# Transceivers.net
KiCad netlist of a schematic drawn in Altium Designer
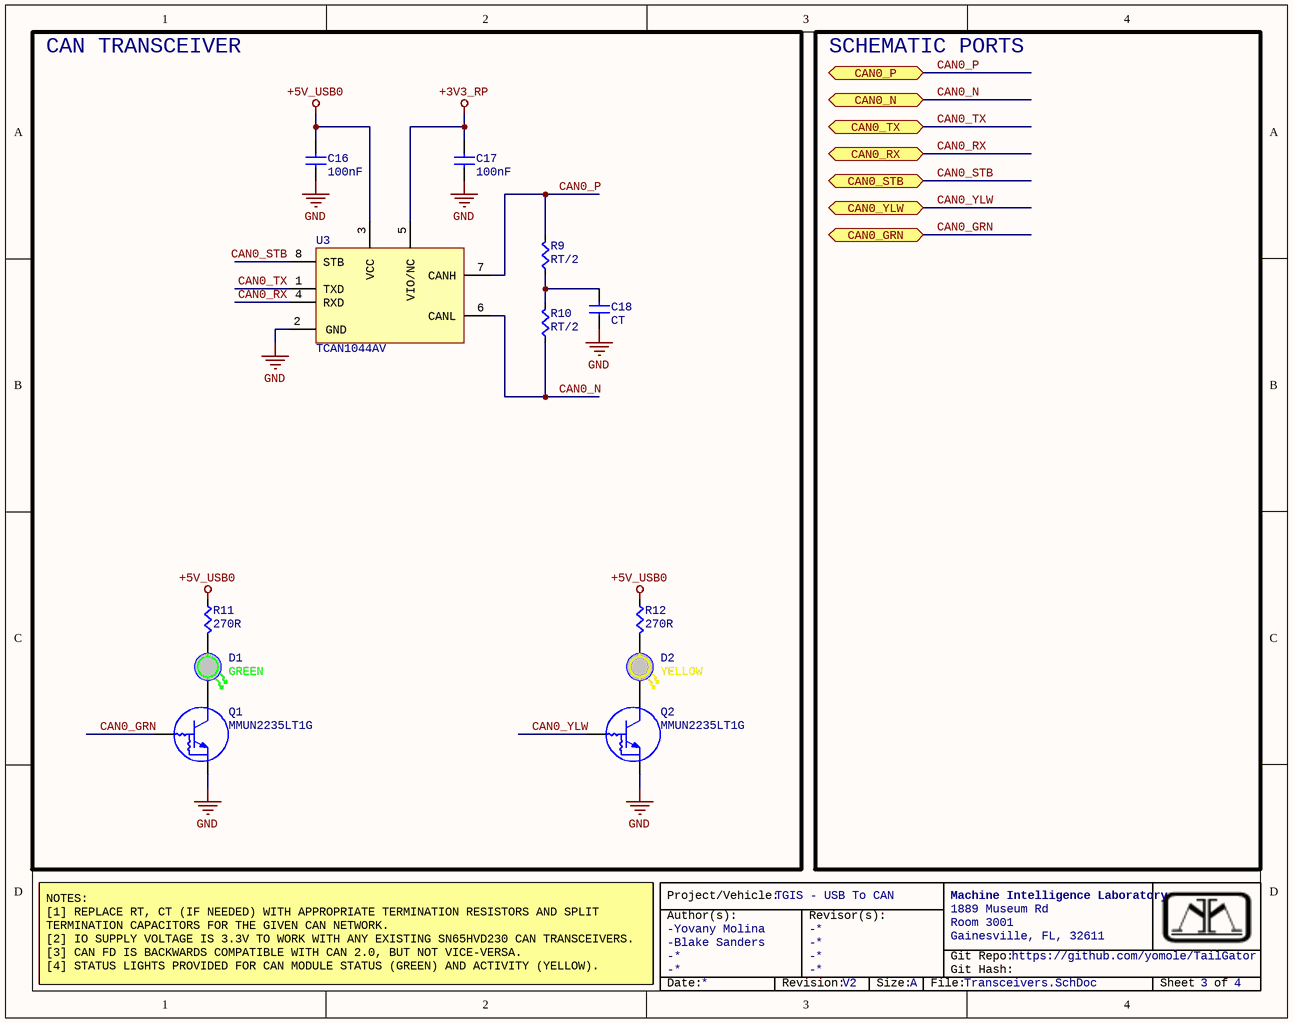
[diagram p0: Transceivers.SchDoc]

(export (version "E")
  (design (tool "Eeschema 10.0.6"))
  (components
    (comp (ref "C16")
      (value "100nF")
      (footprint "CAPC0603")
      (description "Ceramic Capacitor, Multilayer, Cera")
      (fields (field (name "PART NUMBER") "CC0603KRX7R7BB104") (field (name "MANUFACTURER") "Yageo"))
      (libsource (lib "Parts") (part "NP_Capacitor"))
    )
    (comp (ref "C17")
      (value "100nF")
      (footprint "CAPC0603")
      (description "Ceramic Capacitor, Multilayer, Cera")
      (fields (field (name "PART NUMBER") "CC0603KRX7R7BB104") (field (name "MANUFACTURER") "Yageo"))
      (libsource (lib "Parts") (part "NP_Capacitor"))
    )
    (comp (ref "C18")
      (value "CT")
      (footprint "CAPC0603")
      (fields (field (name "Comment") "Cap"))
      (libsource (lib "Passives") (part "Cap"))
    )
    (comp (ref "D1")
      (value "GREEN")
      (footprint "LED0603")
      (description "Single Color LED, Bright Green, Wat")
      (fields (field (name "PART NUMBER") "150060VS75000") (field (name "MANUFACTURER") "Wurth Electronics"))
      (libsource (lib "Parts") (part "LED_Green"))
    )
    (comp (ref "D2")
      (value "YELLOW")
      (footprint "LED0603")
      (description "Single Color LED, Yellow, Water Cle")
      (fields (field (name "PART NUMBER") "150060YS75000") (field (name "MANUFACTURER") "Wurth Electronics"))
      (libsource (lib "Parts") (part "LED_Yellow"))
    )
    (comp (ref "Q1")
      (value "MMUN2235LT1G")
      (footprint "SOT-23-3")
      (description "Small Signal Bipolar Transistor, 0.")
      (fields (field (name "MANUFACTURER") "ON Semiconductor"))
      (libsource (lib "Parts") (part "PB_NPN_Transistor"))
    )
    (comp (ref "Q2")
      (value "MMUN2235LT1G")
      (footprint "SOT-23-3")
      (description "Small Signal Bipolar Transistor, 0.")
      (fields (field (name "MANUFACTURER") "ON Semiconductor"))
      (libsource (lib "Parts") (part "PB_NPN_Transistor"))
    )
    (comp (ref "R9")
      (value "RT/2")
      (footprint "RES0603")
      (fields (field (name "Comment") "Res"))
      (libsource (lib "Passives") (part "Res"))
    )
    (comp (ref "R10")
      (value "RT/2")
      (footprint "RES0603")
      (fields (field (name "Comment") "Res"))
      (libsource (lib "Passives") (part "Res"))
    )
    (comp (ref "R11")
      (value "270R")
      (footprint "RES0603")
      (description "Fixed Resistor, Metal Glaze/thick F")
      (fields (field (name "PART NUMBER") "RC0603FR-07270RL") (field (name "POWER") "100mW"))
      (libsource (lib "Parts") (part "Resistor"))
    )
    (comp (ref "R12")
      (value "270R")
      (footprint "RES0603")
      (description "Fixed Resistor, Metal Glaze/thick F")
      (fields (field (name "PART NUMBER") "RC0603FR-07270RL") (field (name "POWER") "100mW"))
      (libsource (lib "Parts") (part "Resistor"))
    )
    (comp (ref "U3")
      (value "TCAN1044AV")
      (footprint "SOT65P280X110-8N")
      (description "1/1 Transceiver Half CANbus TSOT-23-8")
      (libsource (lib "TGIS_Microcontrollers") (part "TCAN1044AVDDFRQ1"))
    )
  )
  (nets
    (net (code "1") (name "+3V3_RP") (class "Default")
      (node (ref "C17") (pin "2") (pinfunction "B_2") (pintype "passive"))
      (node (ref "U3") (pin "5") (pinfunction "VIO/NC_5") (pintype "passive"))
    )
    (net (code "2") (name "+5V_USB0") (class "Default")
      (node (ref "C16") (pin "2") (pinfunction "B_2") (pintype "passive"))
      (node (ref "R11") (pin "2") (pinfunction "B_2") (pintype "passive"))
      (node (ref "R12") (pin "2") (pinfunction "B_2") (pintype "passive"))
      (node (ref "U3") (pin "3") (pinfunction "VCC_3") (pintype "passive"))
    )
    (net (code "3") (name "/CAN0_GRN") (class "Default")
      (node (ref "Q1") (pin "1") (pinfunction "B_1") (pintype "passive"))
    )
    (net (code "4") (name "/CAN0_N") (class "Default")
      (node (ref "R10") (pin "2") (pinfunction "B_2") (pintype "passive"))
      (node (ref "U3") (pin "6") (pinfunction "CANL_6") (pintype "passive"))
    )
    (net (code "5") (name "/CAN0_P") (class "Default")
      (node (ref "R9") (pin "1") (pinfunction "A_1") (pintype "passive"))
      (node (ref "U3") (pin "7") (pinfunction "CANH_7") (pintype "passive"))
    )
    (net (code "6") (name "/CAN0_RX") (class "Default")
      (node (ref "U3") (pin "4") (pinfunction "RXD_4") (pintype "passive"))
    )
    (net (code "7") (name "/CAN0_STB") (class "Default")
      (node (ref "U3") (pin "8") (pinfunction "STB_8") (pintype "passive"))
    )
    (net (code "8") (name "/CAN0_TX") (class "Default")
      (node (ref "U3") (pin "1") (pinfunction "TXD_1") (pintype "passive"))
    )
    (net (code "9") (name "/CAN0_YLW") (class "Default")
      (node (ref "Q2") (pin "1") (pinfunction "B_1") (pintype "passive"))
    )
    (net (code "10") (name "GND") (class "Default")
      (node (ref "C16") (pin "1") (pinfunction "A_1") (pintype "passive"))
      (node (ref "C17") (pin "1") (pinfunction "A_1") (pintype "passive"))
      (node (ref "C18") (pin "2") (pinfunction "B_2") (pintype "passive"))
      (node (ref "Q1") (pin "2") (pinfunction "E_2") (pintype "passive"))
      (node (ref "Q2") (pin "2") (pinfunction "E_2") (pintype "passive"))
      (node (ref "U3") (pin "2") (pinfunction "GND_2") (pintype "passive"))
    )
    (net (code "11") (name "Net-(C18-A)") (class "Default")
      (node (ref "C18") (pin "1") (pinfunction "A_1") (pintype "passive"))
      (node (ref "R10") (pin "1") (pinfunction "A_1") (pintype "passive"))
      (node (ref "R9") (pin "2") (pinfunction "B_2") (pintype "passive"))
    )
    (net (code "12") (name "Net-(Q1-C)") (class "Default")
      (node (ref "D1") (pin "C") (pinfunction "C_C") (pintype "passive"))
      (node (ref "Q1") (pin "3") (pinfunction "C_3") (pintype "passive"))
    )
    (net (code "13") (name "Net-(Q2-C)") (class "Default")
      (node (ref "D2") (pin "C") (pinfunction "C_C") (pintype "passive"))
      (node (ref "Q2") (pin "3") (pinfunction "C_3") (pintype "passive"))
    )
    (net (code "14") (name "Net-(R11-A)") (class "Default")
      (node (ref "D1") (pin "A") (pinfunction "A_A") (pintype "passive"))
      (node (ref "R11") (pin "1") (pinfunction "A_1") (pintype "passive"))
    )
    (net (code "15") (name "Net-(R12-A)") (class "Default")
      (node (ref "D2") (pin "A") (pinfunction "A_A") (pintype "passive"))
      (node (ref "R12") (pin "1") (pinfunction "A_1") (pintype "passive"))
    )
  )
)
